# clouds_v302_3.net
KiCad netlist of a schematic drawn in Altium Designer
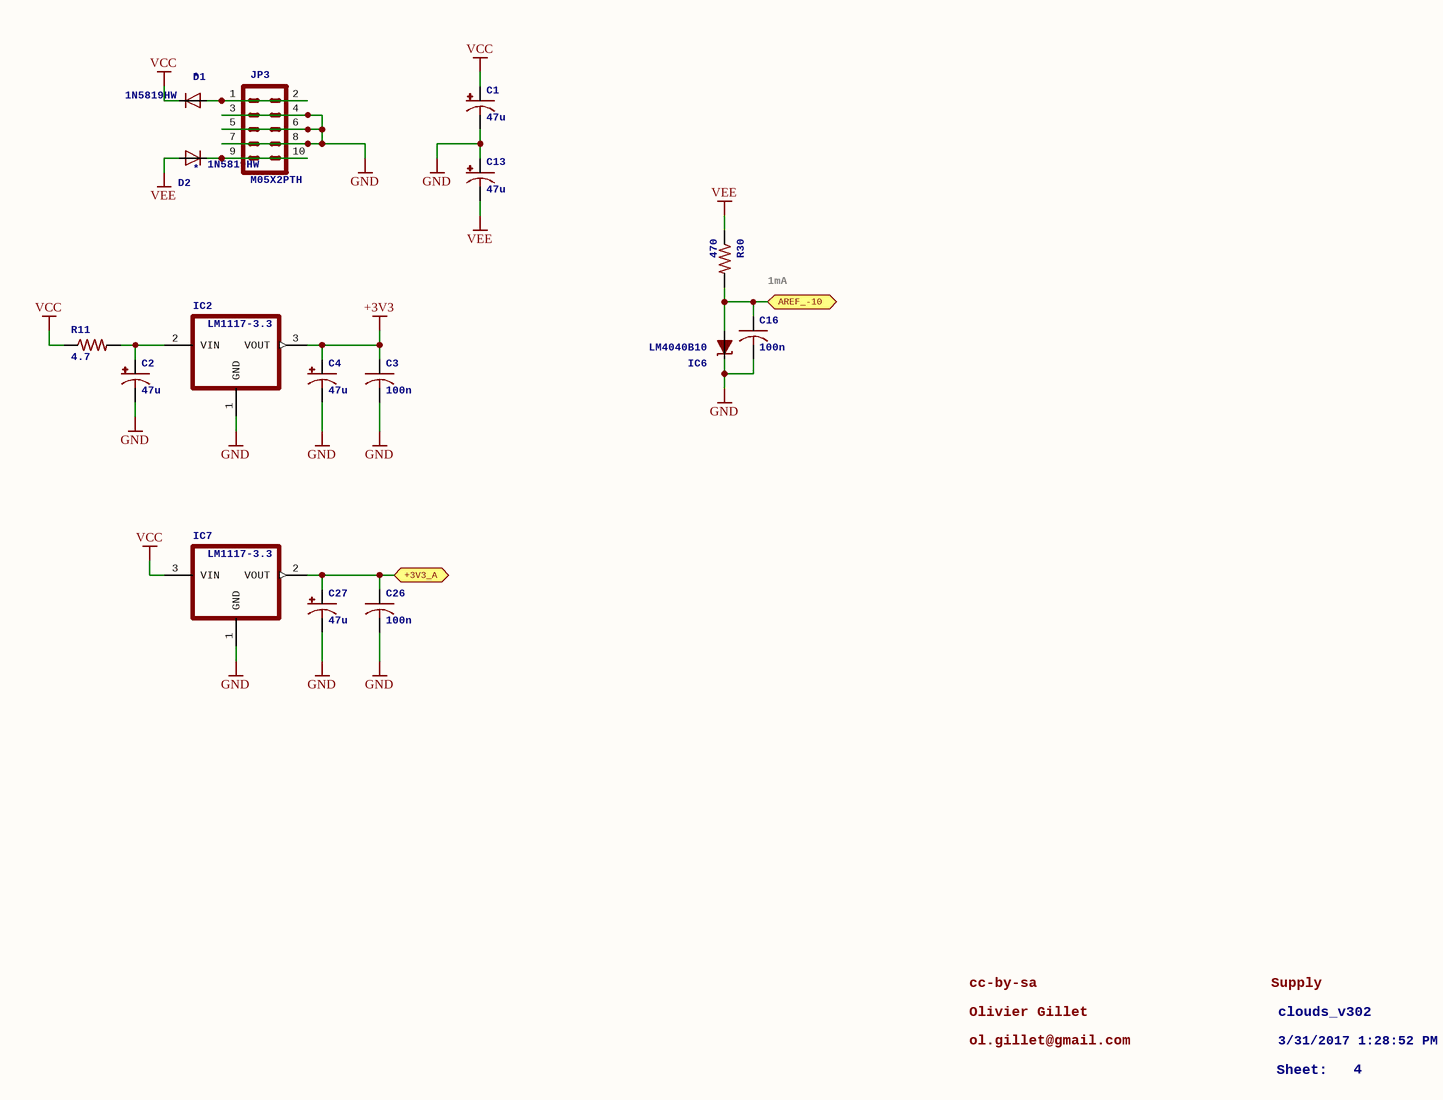
[diagram p0: clouds_v302_3.SchDoc]

(export (version "E")
  (design (tool "Eeschema 10.0.6"))
  (components
    (comp (ref "C1")
      (value "47u")
      (footprint "PANASONIC_D")
      (description "POLARIZED CAPACITOR, American symbol")
      (libsource (lib "rcl") (part "CPOL-USD"))
    )
    (comp (ref "C2")
      (value "47u")
      (footprint "PANASONIC_D")
      (description "POLARIZED CAPACITOR, American symbol")
      (libsource (lib "rcl") (part "CPOL-USD"))
    )
    (comp (ref "C3")
      (value "100n")
      (footprint "C0603")
      (description "CAPACITOR, American symbol")
      (libsource (lib "rcl") (part "C-USC0603"))
    )
    (comp (ref "C4")
      (value "47u")
      (footprint "PANASONIC_D")
      (description "POLARIZED CAPACITOR, American symbol")
      (libsource (lib "rcl") (part "CPOL-USD"))
    )
    (comp (ref "C13")
      (value "47u")
      (footprint "PANASONIC_D")
      (description "POLARIZED CAPACITOR, American symbol")
      (libsource (lib "rcl") (part "CPOL-USD"))
    )
    (comp (ref "C16")
      (value "100n")
      (footprint "C0603")
      (description "CAPACITOR, American symbol")
      (libsource (lib "rcl") (part "C-USC0603"))
    )
    (comp (ref "C26")
      (value "100n")
      (footprint "C0603")
      (description "CAPACITOR, American symbol")
      (libsource (lib "rcl") (part "C-USC0603"))
    )
    (comp (ref "C27")
      (value "47u")
      (footprint "PANASONIC_D")
      (description "POLARIZED CAPACITOR, American symbol")
      (libsource (lib "rcl") (part "CPOL-USD"))
    )
    (comp (ref "D1")
      (value "1N5819HW")
      (footprint "SOD123")
      (description "DIODE")
      (fields (field (name "NAME") "*"))
      (libsource (lib "diode") (part "DIODE-SOD123"))
    )
    (comp (ref "D2")
      (value "1N5819HW")
      (footprint "SOD123")
      (description "DIODE")
      (fields (field (name "NAME") "*"))
      (libsource (lib "diode") (part "DIODE-SOD123"))
    )
    (comp (ref "IC2")
      (value "LM1117-3.3")
      (footprint "TO252")
      (description "800mA and 1A Low Dropout (LDO) Positive Regulator   1.8V, 2.5V, 2.85V, 3.3V, 5V, and Adj")
      (libsource (lib "og-vreg") (part "REG1117T"))
    )
    (comp (ref "IC6")
      (value "LM4040B10")
      (footprint "DBZ_R-PDSO-G3")
      (libsource (lib "texas") (part "LM4041DBZ"))
    )
    (comp (ref "IC7")
      (value "LM1117-3.3")
      (footprint "SOT223")
      (description "800mA and 1A Low Dropout (LDO) Positive Regulator   1.8V, 2.5V, 2.85V, 3.3V, 5V, and Adj")
      (libsource (lib "og-vreg") (part "REG1117"))
    )
    (comp (ref "JP3")
      (value "M05X2PTH")
      (footprint "AVR_ICSP")
      (libsource (lib "og-header") (part "M05X2PTH"))
    )
    (comp (ref "R11")
      (value "4.7")
      (footprint "R1206")
      (description "RESISTOR, American symbol")
      (libsource (lib "rcl") (part "R-US_R1206"))
    )
    (comp (ref "R30")
      (value "470")
      (footprint "R0603")
      (description "RESISTOR, American symbol")
      (libsource (lib "rcl") (part "R-US_R0603"))
    )
  )
  (nets
    (net (code "1") (name "+3V3") (class "Default")
      (node (ref "C3") (pin "1") (pinfunction "1_1") (pintype "passive"))
      (node (ref "C4") (pin "+") (pinfunction "+_+") (pintype "passive"))
      (node (ref "IC2") (pin "3") (pinfunction "VOUT_3") (pintype "output"))
    )
    (net (code "2") (name "/+3V3_A") (class "Default")
      (node (ref "C26") (pin "1") (pinfunction "1_1") (pintype "passive"))
      (node (ref "C27") (pin "+") (pinfunction "+_+") (pintype "passive"))
      (node (ref "IC7") (pin "2") (pinfunction "VOUT_2") (pintype "output"))
    )
    (net (code "3") (name "/AREF_-10") (class "Default")
      (node (ref "C16") (pin "1") (pinfunction "1_1") (pintype "passive"))
      (node (ref "IC6") (pin "2") (pinfunction "A_2") (pintype "passive"))
      (node (ref "R30") (pin "2") (pinfunction "2_2") (pintype "passive"))
    )
    (net (code "4") (name "GND") (class "Default")
      (node (ref "C1") (pin "-") (pinfunction "-_-") (pintype "passive"))
      (node (ref "C13") (pin "+") (pinfunction "+_+") (pintype "passive"))
      (node (ref "C16") (pin "2") (pinfunction "2_2") (pintype "passive"))
      (node (ref "C2") (pin "-") (pinfunction "-_-") (pintype "passive"))
      (node (ref "C26") (pin "2") (pinfunction "2_2") (pintype "passive"))
      (node (ref "C27") (pin "-") (pinfunction "-_-") (pintype "passive"))
      (node (ref "C3") (pin "2") (pinfunction "2_2") (pintype "passive"))
      (node (ref "C4") (pin "-") (pinfunction "-_-") (pintype "passive"))
      (node (ref "IC2") (pin "1") (pinfunction "GND_1") (pintype "power_in"))
      (node (ref "IC6") (pin "1") (pinfunction "C_1") (pintype "passive"))
      (node (ref "IC7") (pin "1") (pinfunction "GND_1") (pintype "power_in"))
      (node (ref "JP3") (pin "3") (pinfunction "3_3") (pintype "passive"))
      (node (ref "JP3") (pin "4") (pinfunction "4_4") (pintype "passive"))
      (node (ref "JP3") (pin "5") (pinfunction "5_5") (pintype "passive"))
      (node (ref "JP3") (pin "6") (pinfunction "6_6") (pintype "passive"))
      (node (ref "JP3") (pin "7") (pinfunction "7_7") (pintype "passive"))
      (node (ref "JP3") (pin "8") (pinfunction "8_8") (pintype "passive"))
    )
    (net (code "5") (name "Net-(D1-PadA)") (class "Default")
      (node (ref "D1") (pin "A") (pinfunction "A_A") (pintype "passive"))
      (node (ref "JP3") (pin "1") (pinfunction "1_1") (pintype "passive"))
      (node (ref "JP3") (pin "2") (pinfunction "2_2") (pintype "passive"))
    )
    (net (code "6") (name "Net-(D2-PadC)") (class "Default")
      (node (ref "D2") (pin "C") (pinfunction "C_C") (pintype "passive"))
      (node (ref "JP3") (pin "10") (pinfunction "10_10") (pintype "passive"))
      (node (ref "JP3") (pin "9") (pinfunction "9_9") (pintype "passive"))
    )
    (net (code "7") (name "Net-(IC2-VIN)") (class "Default")
      (node (ref "C2") (pin "+") (pinfunction "+_+") (pintype "passive"))
      (node (ref "IC2") (pin "2") (pinfunction "VIN_2") (pintype "passive"))
      (node (ref "R11") (pin "2") (pinfunction "2_2") (pintype "passive"))
    )
    (net (code "8") (name "VCC") (class "Default")
      (node (ref "C1") (pin "+") (pinfunction "+_+") (pintype "passive"))
      (node (ref "D1") (pin "C") (pinfunction "C_C") (pintype "passive"))
      (node (ref "IC7") (pin "3") (pinfunction "VIN_3") (pintype "passive"))
      (node (ref "R11") (pin "1") (pinfunction "1_1") (pintype "passive"))
    )
    (net (code "9") (name "VEE") (class "Default")
      (node (ref "C13") (pin "-") (pinfunction "-_-") (pintype "passive"))
      (node (ref "D2") (pin "A") (pinfunction "A_A") (pintype "passive"))
      (node (ref "R30") (pin "1") (pinfunction "1_1") (pintype "passive"))
    )
  )
)
